# vco.net
KiCad netlist of a schematic drawn in Altium Designer
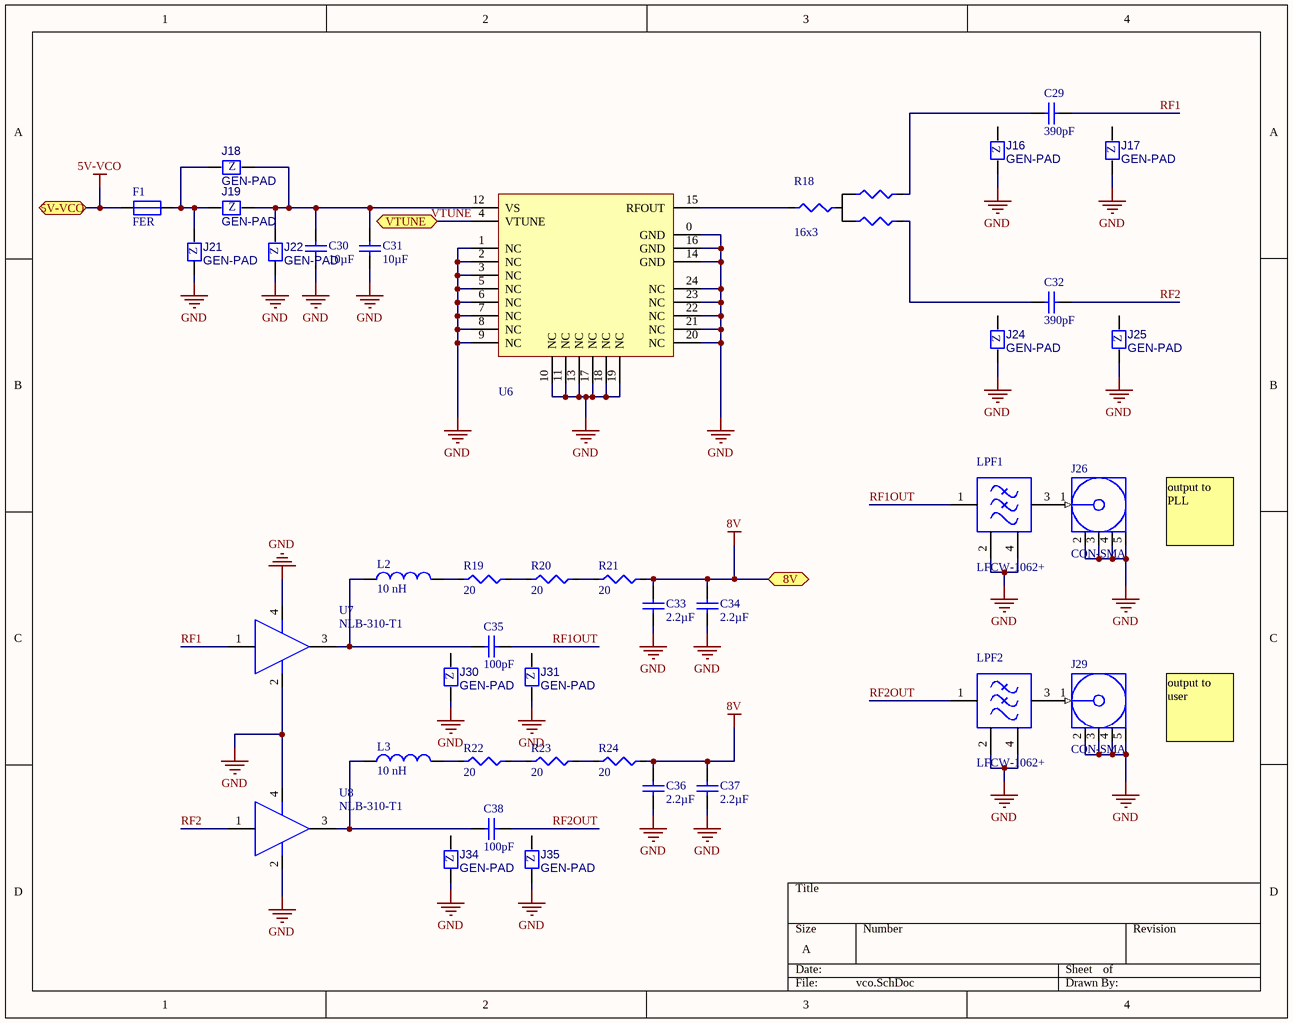
[diagram p0: vco.SchDoc]

(export (version "E")
  (design (tool "Eeschema 10.0.6"))
  (components
    (comp (ref "C29")
      (value "390pF")
      (footprint "0402-RF-0.55mm")
      (description "Capacitor")
      (fields (field (name "EE PART NUMBER") "EE-CAP-00016") (field (name "VOLTAGE") "50V"))
      (libsource (lib "EE") (part "CAP"))
    )
    (comp (ref "C30")
      (value "10µF")
      (footprint "0402-0.55mm")
      (description "Capacitor")
      (fields (field (name "EE PART NUMBER") "EE-CAP-00009") (field (name "VOLTAGE") "10V"))
      (libsource (lib "EE") (part "CAP"))
    )
    (comp (ref "C31")
      (value "10µF")
      (footprint "0402-0.55mm")
      (description "Capacitor")
      (fields (field (name "EE PART NUMBER") "EE-CAP-00009") (field (name "VOLTAGE") "10V"))
      (libsource (lib "EE") (part "CAP"))
    )
    (comp (ref "C32")
      (value "390pF")
      (footprint "0402-RF-0.55mm")
      (description "Capacitor")
      (fields (field (name "EE PART NUMBER") "EE-CAP-00016") (field (name "VOLTAGE") "50V"))
      (libsource (lib "EE") (part "CAP"))
    )
    (comp (ref "C33")
      (value "2.2µF")
      (footprint "0402-0.55mm")
      (description "Capacitor")
      (fields (field (name "EE PART NUMBER") "EE-CAP-00003") (field (name "VOLTAGE") "35V"))
      (libsource (lib "EE") (part "CAP"))
    )
    (comp (ref "C34")
      (value "2.2µF")
      (footprint "0402-0.55mm")
      (description "Capacitor")
      (fields (field (name "EE PART NUMBER") "EE-CAP-00003") (field (name "VOLTAGE") "35V"))
      (libsource (lib "EE") (part "CAP"))
    )
    (comp (ref "C35")
      (value "100pF")
      (footprint "0402-RF-0.55mm")
      (description "Capacitor")
      (fields (field (name "EE PART NUMBER") "EE-CAP-00017") (field (name "VOLTAGE") "25V"))
      (libsource (lib "EE") (part "CAP"))
    )
    (comp (ref "C36")
      (value "2.2µF")
      (footprint "0402-0.55mm")
      (description "Capacitor")
      (fields (field (name "EE PART NUMBER") "EE-CAP-00003") (field (name "VOLTAGE") "35V"))
      (libsource (lib "EE") (part "CAP"))
    )
    (comp (ref "C37")
      (value "2.2µF")
      (footprint "0402-0.55mm")
      (description "Capacitor")
      (fields (field (name "EE PART NUMBER") "EE-CAP-00003") (field (name "VOLTAGE") "35V"))
      (libsource (lib "EE") (part "CAP"))
    )
    (comp (ref "C38")
      (value "100pF")
      (footprint "0402-RF-0.55mm")
      (description "Capacitor")
      (fields (field (name "EE PART NUMBER") "EE-CAP-00017") (field (name "VOLTAGE") "25V"))
      (libsource (lib "EE") (part "CAP"))
    )
    (comp (ref "F1")
      (value "FER")
      (footprint "0603-0.8mm")
      (fields
        (field (name "EE PART NUMBER") "EE-FER-00001")
        (field (name "MANUFACTURER") "Laird-Signal")
        (field (name "MANUFACTURER PART NUMBER") "HZ0603A222R-10")
      )
      (libsource (lib "EE") (part "FER"))
    )
    (comp (ref "J16")
      (value "GEN-PAD")
      (footprint "0402-DNP")
      (description "Generic Component")
      (fields (field (name "EE PART NUMBER") "EE-GEN-00002"))
      (libsource (lib "EE") (part "GEN-PAD"))
    )
    (comp (ref "J17")
      (value "GEN-PAD")
      (footprint "0402-DNP")
      (description "Generic Component")
      (fields (field (name "EE PART NUMBER") "EE-GEN-00002"))
      (libsource (lib "EE") (part "GEN-PAD"))
    )
    (comp (ref "J18")
      (value "GEN-PAD")
      (footprint "0805-DNP")
      (description "Generic Component")
      (fields (field (name "EE PART NUMBER") "EE-GEN-00001"))
      (libsource (lib "EE") (part "GEN-PAD"))
    )
    (comp (ref "J19")
      (value "GEN-PAD")
      (footprint "0805-DNP")
      (description "Generic Component")
      (fields (field (name "EE PART NUMBER") "EE-GEN-00001"))
      (libsource (lib "EE") (part "GEN-PAD"))
    )
    (comp (ref "J21")
      (value "GEN-PAD")
      (footprint "0805-DNP")
      (description "Generic Component")
      (fields (field (name "EE PART NUMBER") "EE-GEN-00001"))
      (libsource (lib "EE") (part "GEN-PAD"))
    )
    (comp (ref "J22")
      (value "GEN-PAD")
      (footprint "0805-DNP")
      (description "Generic Component")
      (fields (field (name "EE PART NUMBER") "EE-GEN-00001"))
      (libsource (lib "EE") (part "GEN-PAD"))
    )
    (comp (ref "J24")
      (value "GEN-PAD")
      (footprint "0402-DNP")
      (description "Generic Component")
      (fields (field (name "EE PART NUMBER") "EE-GEN-00002"))
      (libsource (lib "EE") (part "GEN-PAD"))
    )
    (comp (ref "J25")
      (value "GEN-PAD")
      (footprint "0402-DNP")
      (description "Generic Component")
      (fields (field (name "EE PART NUMBER") "EE-GEN-00002"))
      (libsource (lib "EE") (part "GEN-PAD"))
    )
    (comp (ref "J26")
      (value "CON-SMA")
      (footprint "CON-COAX")
      (fields
        (field (name "EE PART NUMBER") "EE-CON-00001")
        (field (name "MANUFACTURER") "East Coast Microwave")
        (field (name "MANUFACTURER PART NUMBER") "PSF-S01-008")
      )
      (libsource (lib "EE") (part "CON-SMA"))
    )
    (comp (ref "J29")
      (value "CON-SMA")
      (footprint "CON-COAX")
      (fields
        (field (name "EE PART NUMBER") "EE-CON-00001")
        (field (name "MANUFACTURER") "East Coast Microwave")
        (field (name "MANUFACTURER PART NUMBER") "PSF-S01-008")
      )
      (libsource (lib "EE") (part "CON-SMA"))
    )
    (comp (ref "J30")
      (value "GEN-PAD")
      (footprint "0402-DNP")
      (description "Generic Component")
      (fields (field (name "EE PART NUMBER") "EE-GEN-00002"))
      (libsource (lib "EE") (part "GEN-PAD"))
    )
    (comp (ref "J31")
      (value "GEN-PAD")
      (footprint "0402-DNP")
      (description "Generic Component")
      (fields (field (name "EE PART NUMBER") "EE-GEN-00002"))
      (libsource (lib "EE") (part "GEN-PAD"))
    )
    (comp (ref "J34")
      (value "GEN-PAD")
      (footprint "0402-DNP")
      (description "Generic Component")
      (fields (field (name "EE PART NUMBER") "EE-GEN-00002"))
      (libsource (lib "EE") (part "GEN-PAD"))
    )
    (comp (ref "J35")
      (value "GEN-PAD")
      (footprint "0402-DNP")
      (description "Generic Component")
      (fields (field (name "EE PART NUMBER") "EE-GEN-00002"))
      (libsource (lib "EE") (part "GEN-PAD"))
    )
    (comp (ref "L2")
      (value "10 nH")
      (footprint "L0603-0.8mm")
      (description "Inductor")
      (fields (field (name "EE PART NUMBER") "EE-L-00001") (field (name "TOLERANCE") "±2%"))
      (libsource (lib "EE") (part "L"))
    )
    (comp (ref "L3")
      (value "10 nH")
      (footprint "L0603-0.8mm")
      (description "Inductor")
      (fields (field (name "EE PART NUMBER") "EE-L-00001") (field (name "TOLERANCE") "±2%"))
      (libsource (lib "EE") (part "L"))
    )
    (comp (ref "LPF1")
      (value "LFCW-1062+")
      (footprint "LPF-0603-0.8mm")
      (fields
        (field (name "EE PART NUMBER") "EE-FILTER-00001")
        (field (name "POWER") "4W")
        (field (name "MANUFACTURER") "Mini-Circuits")
      )
      (libsource (lib "EE") (part "LPF-LFCW-1062"))
    )
    (comp (ref "LPF2")
      (value "LFCW-1062+")
      (footprint "LPF-0603-0.8mm")
      (fields
        (field (name "EE PART NUMBER") "EE-FILTER-00001")
        (field (name "POWER") "4W")
        (field (name "MANUFACTURER") "Mini-Circuits")
      )
      (libsource (lib "EE") (part "LPF-LFCW-1062"))
    )
    (comp (ref "R18")
      (value "16x3")
      (footprint "0402-SPLIT-3-0.55mm")
      (fields
        (field (name "EE PART NUMBER") "EE-RES-00003")
        (field (name "TOLERANCE") "±1%")
        (field (name "POWER") "0.1W, 1/10W")
      )
      (libsource (lib "EE") (part "RES-SPLIT-3"))
    )
    (comp (ref "R19")
      (value "20")
      (footprint "0805-0.45MM")
      (fields
        (field (name "EM PART NUMBER") "EM-RES-01452")
        (field (name "TOLERANCE") "1%")
        (field (name "POWER") "0.125W")
      )
      (libsource (lib "EM") (part "RES"))
    )
    (comp (ref "R20")
      (value "20")
      (footprint "0805-0.45MM")
      (fields
        (field (name "EM PART NUMBER") "EM-RES-01452")
        (field (name "TOLERANCE") "1%")
        (field (name "POWER") "0.125W")
      )
      (libsource (lib "EM") (part "RES"))
    )
    (comp (ref "R21")
      (value "20")
      (footprint "0805-0.45MM")
      (fields
        (field (name "EM PART NUMBER") "EM-RES-01452")
        (field (name "TOLERANCE") "1%")
        (field (name "POWER") "0.125W")
      )
      (libsource (lib "EM") (part "RES"))
    )
    (comp (ref "R22")
      (value "20")
      (footprint "0805-0.45MM")
      (fields
        (field (name "EM PART NUMBER") "EM-RES-01452")
        (field (name "TOLERANCE") "1%")
        (field (name "POWER") "0.125W")
      )
      (libsource (lib "EM") (part "RES"))
    )
    (comp (ref "R23")
      (value "20")
      (footprint "0805-0.45MM")
      (fields
        (field (name "EM PART NUMBER") "EM-RES-01452")
        (field (name "TOLERANCE") "1%")
        (field (name "POWER") "0.125W")
      )
      (libsource (lib "EM") (part "RES"))
    )
    (comp (ref "R24")
      (value "20")
      (footprint "0805-0.45MM")
      (fields
        (field (name "EM PART NUMBER") "EM-RES-01452")
        (field (name "TOLERANCE") "1%")
        (field (name "POWER") "0.125W")
      )
      (libsource (lib "EM") (part "RES"))
    )
    (comp (ref "U6")
      (value "RFVC1801")
      (footprint "QFN-24-(4x4)")
      (fields
        (field (name "EE PART NUMBER") "EE-MISC-00001")
        (field (name "VOLTAGE") "5.5V")
        (field (name "MANUFACTURER") "RFMD")
      )
      (libsource (lib "EE") (part "RFVC1801"))
    )
    (comp (ref "U7")
      (value "NLB-310-T1")
      (footprint "SOT-86")
      (fields
        (field (name "EE PART NUMBER") "EE-OPAMP-00001")
        (field (name "VOLTAGE") "4.4 V ~ 4.8 V")
        (field (name "MANUFACTURER") "RFMD")
      )
      (libsource (lib "EE") (part "NLB-310"))
    )
    (comp (ref "U8")
      (value "NLB-310-T1")
      (footprint "SOT-86")
      (fields
        (field (name "EE PART NUMBER") "EE-OPAMP-00001")
        (field (name "VOLTAGE") "4.4 V ~ 4.8 V")
        (field (name "MANUFACTURER") "RFMD")
      )
      (libsource (lib "EE") (part "NLB-310"))
    )
  )
  (nets
    (net (code "1") (name "/RF1") (class "Default")
      (node (ref "C29") (pin "2") (pinfunction "2_2") (pintype "passive"))
      (node (ref "U7") (pin "1") (pinfunction "RFIN_1") (pintype "passive"))
    )
    (net (code "2") (name "/RF1OUT") (class "Default")
      (node (ref "C35") (pin "2") (pinfunction "2_2") (pintype "passive"))
      (node (ref "LPF1") (pin "1") (pinfunction "RF-IN_1") (pintype "passive"))
    )
    (net (code "3") (name "/RF2") (class "Default")
      (node (ref "C32") (pin "2") (pinfunction "2_2") (pintype "passive"))
      (node (ref "U8") (pin "1") (pinfunction "RFIN_1") (pintype "passive"))
    )
    (net (code "4") (name "/RF2OUT") (class "Default")
      (node (ref "C38") (pin "2") (pinfunction "2_2") (pintype "passive"))
      (node (ref "LPF2") (pin "1") (pinfunction "RF-IN_1") (pintype "passive"))
    )
    (net (code "5") (name "/VTUNE") (class "Default")
      (node (ref "U6") (pin "4") (pinfunction "VTUNE_4") (pintype "power_in"))
    )
    (net (code "6") (name "5V-VCO") (class "Default")
      (node (ref "F1") (pin "2") (pinfunction "2_2") (pintype "passive"))
    )
    (net (code "7") (name "8V") (class "Default")
      (node (ref "C33") (pin "2") (pinfunction "2_2") (pintype "passive"))
      (node (ref "C34") (pin "2") (pinfunction "2_2") (pintype "passive"))
      (node (ref "C36") (pin "2") (pinfunction "2_2") (pintype "passive"))
      (node (ref "C37") (pin "2") (pinfunction "2_2") (pintype "passive"))
      (node (ref "R21") (pin "2") (pinfunction "2_2") (pintype "passive"))
      (node (ref "R24") (pin "2") (pinfunction "2_2") (pintype "passive"))
    )
    (net (code "8") (name "GND") (class "Default")
      (node (ref "C30") (pin "1") (pinfunction "1_1") (pintype "passive"))
      (node (ref "C31") (pin "1") (pinfunction "1_1") (pintype "passive"))
      (node (ref "C33") (pin "1") (pinfunction "1_1") (pintype "passive"))
      (node (ref "C34") (pin "1") (pinfunction "1_1") (pintype "passive"))
      (node (ref "C36") (pin "1") (pinfunction "1_1") (pintype "passive"))
      (node (ref "C37") (pin "1") (pinfunction "1_1") (pintype "passive"))
      (node (ref "J16") (pin "2") (pinfunction "2_2") (pintype "passive"))
      (node (ref "J17") (pin "2") (pinfunction "2_2") (pintype "passive"))
      (node (ref "J21") (pin "2") (pinfunction "2_2") (pintype "passive"))
      (node (ref "J22") (pin "2") (pinfunction "2_2") (pintype "passive"))
      (node (ref "J24") (pin "2") (pinfunction "2_2") (pintype "passive"))
      (node (ref "J25") (pin "2") (pinfunction "2_2") (pintype "passive"))
      (node (ref "J26") (pin "2") (pinfunction "GND_2") (pintype "power_in"))
      (node (ref "J26") (pin "3") (pinfunction "GND_3") (pintype "power_in"))
      (node (ref "J26") (pin "4") (pinfunction "GND_4") (pintype "power_in"))
      (node (ref "J26") (pin "5") (pinfunction "GND_5") (pintype "power_in"))
      (node (ref "J29") (pin "2") (pinfunction "GND_2") (pintype "power_in"))
      (node (ref "J29") (pin "3") (pinfunction "GND_3") (pintype "power_in"))
      (node (ref "J29") (pin "4") (pinfunction "GND_4") (pintype "power_in"))
      (node (ref "J29") (pin "5") (pinfunction "GND_5") (pintype "power_in"))
      (node (ref "J30") (pin "2") (pinfunction "2_2") (pintype "passive"))
      (node (ref "J31") (pin "2") (pinfunction "2_2") (pintype "passive"))
      (node (ref "J34") (pin "2") (pinfunction "2_2") (pintype "passive"))
      (node (ref "J35") (pin "2") (pinfunction "2_2") (pintype "passive"))
      (node (ref "LPF1") (pin "2") (pinfunction "GND_2") (pintype "passive"))
      (node (ref "LPF1") (pin "4") (pinfunction "GND_4") (pintype "passive"))
      (node (ref "LPF2") (pin "2") (pinfunction "GND_2") (pintype "passive"))
      (node (ref "LPF2") (pin "4") (pinfunction "GND_4") (pintype "passive"))
      (node (ref "U6") (pin "0") (pinfunction "GND_0") (pintype "power_in"))
      (node (ref "U6") (pin "1") (pinfunction "NC_1") (pintype "power_in"))
      (node (ref "U6") (pin "10") (pinfunction "NC_10") (pintype "power_in"))
      (node (ref "U6") (pin "11") (pinfunction "NC_11") (pintype "power_in"))
      (node (ref "U6") (pin "13") (pinfunction "NC_13") (pintype "power_in"))
      (node (ref "U6") (pin "14") (pinfunction "GND_14") (pintype "power_in"))
      (node (ref "U6") (pin "16") (pinfunction "GND_16") (pintype "power_in"))
      (node (ref "U6") (pin "17") (pinfunction "NC_17") (pintype "power_in"))
      (node (ref "U6") (pin "18") (pinfunction "NC_18") (pintype "power_in"))
      (node (ref "U6") (pin "19") (pinfunction "NC_19") (pintype "power_in"))
      (node (ref "U6") (pin "2") (pinfunction "NC_2") (pintype "power_in"))
      (node (ref "U6") (pin "20") (pinfunction "NC_20") (pintype "power_in"))
      (node (ref "U6") (pin "21") (pinfunction "NC_21") (pintype "power_in"))
      (node (ref "U6") (pin "22") (pinfunction "NC_22") (pintype "power_in"))
      (node (ref "U6") (pin "23") (pinfunction "NC_23") (pintype "power_in"))
      (node (ref "U6") (pin "24") (pinfunction "NC_24") (pintype "power_in"))
      (node (ref "U6") (pin "3") (pinfunction "NC_3") (pintype "power_in"))
      (node (ref "U6") (pin "5") (pinfunction "NC_5") (pintype "power_in"))
      (node (ref "U6") (pin "6") (pinfunction "NC_6") (pintype "power_in"))
      (node (ref "U6") (pin "7") (pinfunction "NC_7") (pintype "power_in"))
      (node (ref "U6") (pin "8") (pinfunction "NC_8") (pintype "power_in"))
      (node (ref "U6") (pin "9") (pinfunction "NC_9") (pintype "power_in"))
      (node (ref "U7") (pin "2") (pinfunction "GND_2") (pintype "power_in"))
      (node (ref "U7") (pin "4") (pinfunction "GND_4") (pintype "power_in"))
      (node (ref "U8") (pin "2") (pinfunction "GND_2") (pintype "power_in"))
      (node (ref "U8") (pin "4") (pinfunction "GND_4") (pintype "power_in"))
    )
    (net (code "9") (name "Net-(C29-Pad1)") (class "Default")
      (node (ref "C29") (pin "1") (pinfunction "1_1") (pintype "passive"))
      (node (ref "R18") (pin "2") (pinfunction "2_2") (pintype "passive"))
    )
    (net (code "10") (name "Net-(C32-Pad1)") (class "Default")
      (node (ref "C32") (pin "1") (pinfunction "1_1") (pintype "passive"))
      (node (ref "R18") (pin "3") (pinfunction "3_3") (pintype "passive"))
    )
    (net (code "11") (name "Net-(F1-Pad1)") (class "Default")
      (node (ref "F1") (pin "1") (pinfunction "1_1") (pintype "passive"))
      (node (ref "J18") (pin "2") (pinfunction "2_2") (pintype "passive"))
      (node (ref "J19") (pin "2") (pinfunction "2_2") (pintype "passive"))
      (node (ref "J21") (pin "1") (pinfunction "1_1") (pintype "passive"))
    )
    (net (code "12") (name "Net-(J26-Signal)") (class "Default")
      (node (ref "J26") (pin "1") (pinfunction "Signal_1") (pintype "input"))
      (node (ref "LPF1") (pin "3") (pinfunction "RF-OUT_3") (pintype "passive"))
    )
    (net (code "13") (name "Net-(J29-Signal)") (class "Default")
      (node (ref "J29") (pin "1") (pinfunction "Signal_1") (pintype "input"))
      (node (ref "LPF2") (pin "3") (pinfunction "RF-OUT_3") (pintype "passive"))
    )
    (net (code "14") (name "Net-(L2-Pad2)") (class "Default")
      (node (ref "L2") (pin "2") (pinfunction "2_2") (pintype "passive"))
      (node (ref "R19") (pin "1") (pinfunction "1_1") (pintype "passive"))
    )
    (net (code "15") (name "Net-(L3-Pad2)") (class "Default")
      (node (ref "L3") (pin "2") (pinfunction "2_2") (pintype "passive"))
      (node (ref "R22") (pin "1") (pinfunction "1_1") (pintype "passive"))
    )
    (net (code "16") (name "Net-(R19-Pad2)") (class "Default")
      (node (ref "R19") (pin "2") (pinfunction "2_2") (pintype "passive"))
      (node (ref "R20") (pin "1") (pinfunction "1_1") (pintype "passive"))
    )
    (net (code "17") (name "Net-(R20-Pad2)") (class "Default")
      (node (ref "R20") (pin "2") (pinfunction "2_2") (pintype "passive"))
      (node (ref "R21") (pin "1") (pinfunction "1_1") (pintype "passive"))
    )
    (net (code "18") (name "Net-(R22-Pad2)") (class "Default")
      (node (ref "R22") (pin "2") (pinfunction "2_2") (pintype "passive"))
      (node (ref "R23") (pin "1") (pinfunction "1_1") (pintype "passive"))
    )
    (net (code "19") (name "Net-(R23-Pad2)") (class "Default")
      (node (ref "R23") (pin "2") (pinfunction "2_2") (pintype "passive"))
      (node (ref "R24") (pin "1") (pinfunction "1_1") (pintype "passive"))
    )
    (net (code "20") (name "Net-(U6-RFOUT)") (class "Default")
      (node (ref "R18") (pin "1") (pinfunction "1_1") (pintype "passive"))
      (node (ref "U6") (pin "15") (pinfunction "RFOUT_15") (pintype "power_in"))
    )
    (net (code "21") (name "Net-(U6-VS)") (class "Default")
      (node (ref "C30") (pin "2") (pinfunction "2_2") (pintype "passive"))
      (node (ref "C31") (pin "2") (pinfunction "2_2") (pintype "passive"))
      (node (ref "J18") (pin "1") (pinfunction "1_1") (pintype "passive"))
      (node (ref "J19") (pin "1") (pinfunction "1_1") (pintype "passive"))
      (node (ref "J22") (pin "1") (pinfunction "1_1") (pintype "passive"))
      (node (ref "U6") (pin "12") (pinfunction "VS_12") (pintype "power_in"))
    )
    (net (code "22") (name "Net-(U7-RFOUT)") (class "Default")
      (node (ref "C35") (pin "1") (pinfunction "1_1") (pintype "passive"))
      (node (ref "L2") (pin "1") (pinfunction "1_1") (pintype "passive"))
      (node (ref "U7") (pin "3") (pinfunction "RFOUT_3") (pintype "passive"))
    )
    (net (code "23") (name "Net-(U8-RFOUT)") (class "Default")
      (node (ref "C38") (pin "1") (pinfunction "1_1") (pintype "passive"))
      (node (ref "L3") (pin "1") (pinfunction "1_1") (pintype "passive"))
      (node (ref "U8") (pin "3") (pinfunction "RFOUT_3") (pintype "passive"))
    )
    (net (code "24") (name "unconnected-(J16-Pad1)") (class "Default")
      (node (ref "J16") (pin "1") (pinfunction "1_1") (pintype "passive"))
    )
    (net (code "25") (name "unconnected-(J17-Pad1)") (class "Default")
      (node (ref "J17") (pin "1") (pinfunction "1_1") (pintype "passive"))
    )
    (net (code "26") (name "unconnected-(J24-Pad1)") (class "Default")
      (node (ref "J24") (pin "1") (pinfunction "1_1") (pintype "passive"))
    )
    (net (code "27") (name "unconnected-(J25-Pad1)") (class "Default")
      (node (ref "J25") (pin "1") (pinfunction "1_1") (pintype "passive"))
    )
    (net (code "28") (name "unconnected-(J30-Pad1)") (class "Default")
      (node (ref "J30") (pin "1") (pinfunction "1_1") (pintype "passive"))
    )
    (net (code "29") (name "unconnected-(J31-Pad1)") (class "Default")
      (node (ref "J31") (pin "1") (pinfunction "1_1") (pintype "passive"))
    )
    (net (code "30") (name "unconnected-(J34-Pad1)") (class "Default")
      (node (ref "J34") (pin "1") (pinfunction "1_1") (pintype "passive"))
    )
    (net (code "31") (name "unconnected-(J35-Pad1)") (class "Default")
      (node (ref "J35") (pin "1") (pinfunction "1_1") (pintype "passive"))
    )
  )
)
